# CIRULO_PANEL.net
KiCad netlist of a schematic drawn in EAGLE
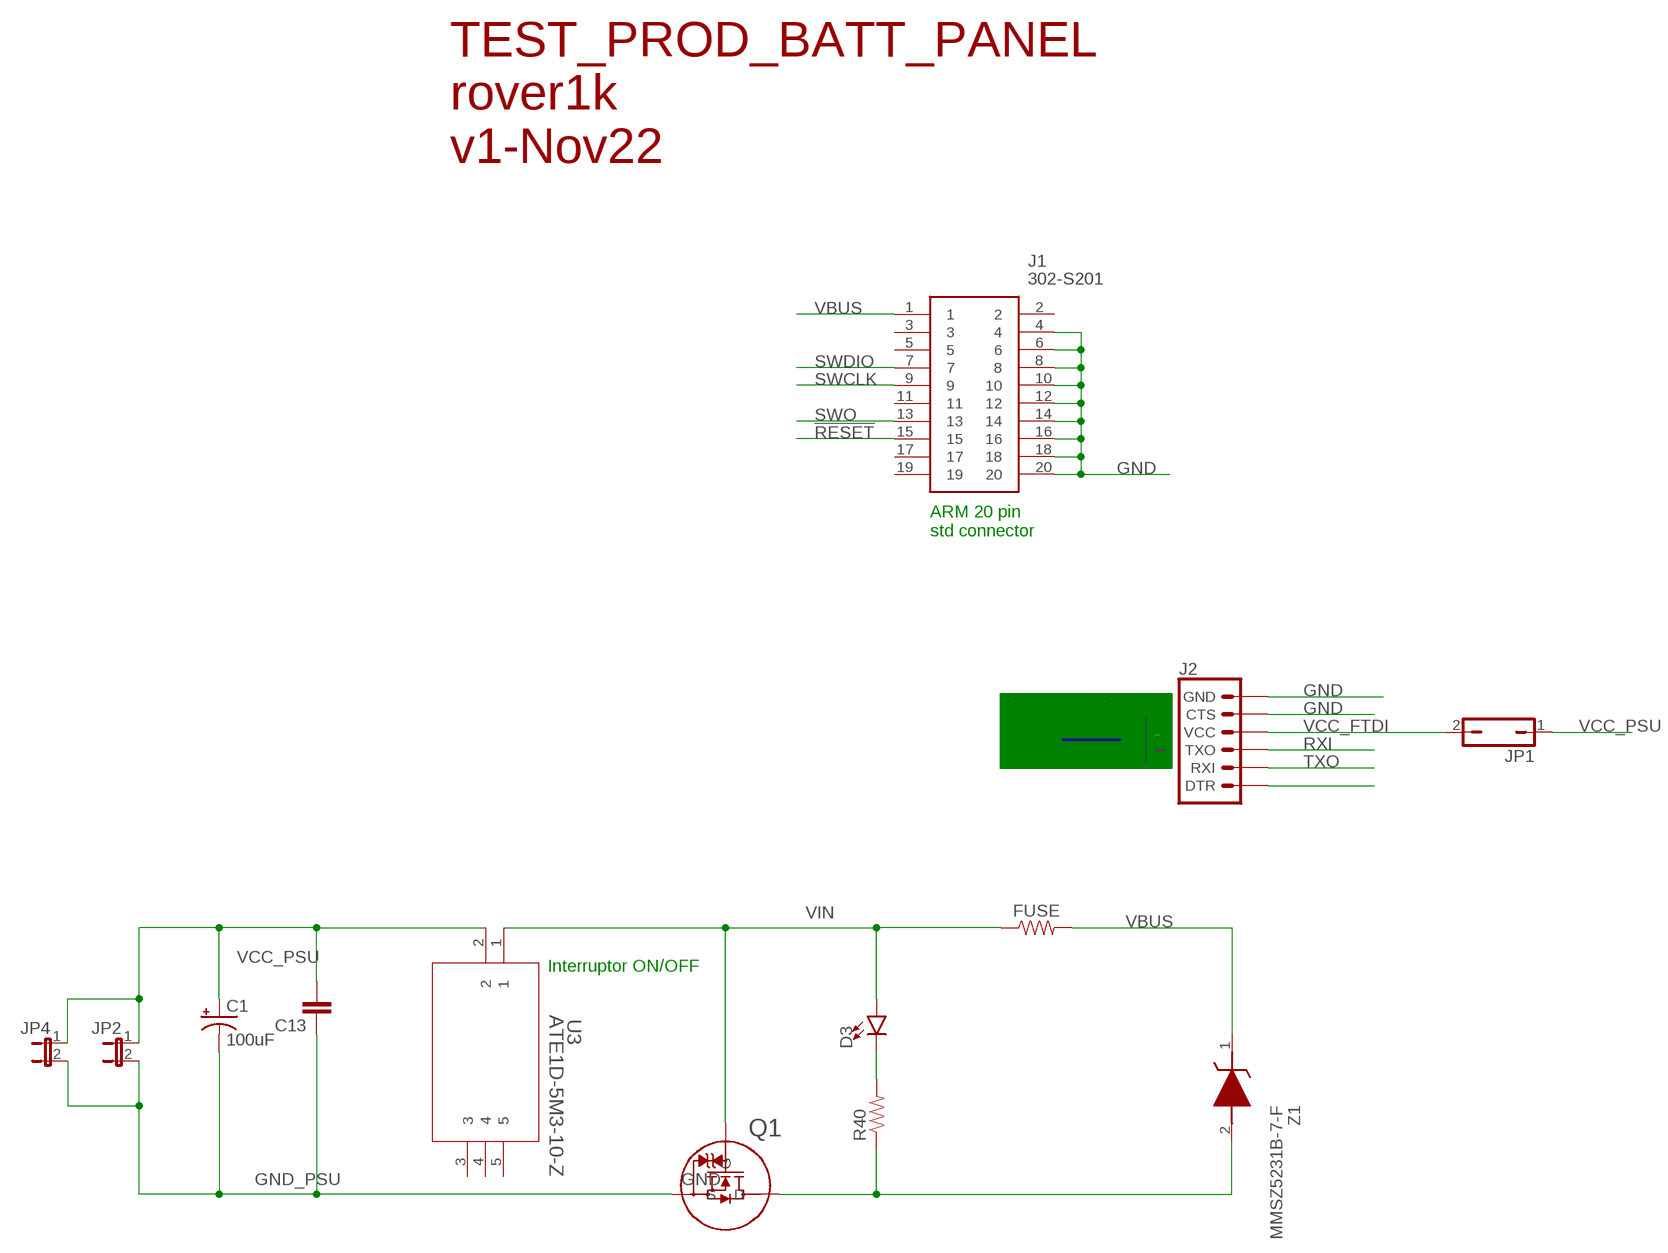
[diagram p0: schematic, sheet 1]

(export (version "E")
  (design (tool "Eeschema 10.0.6"))
  (components
    (comp (ref "C1")
      (value "100uF")
      (footprint "eagle-import:CPOL-RADIAL-2.5MM-6.5MM")
      (libsource (lib "eagle-import") (part "100UF-POLAR-RADIAL-2.5MM-25V-20%"))
    )
    (comp (ref "C13")
      (value "C-EUC0805")
      (footprint "eagle-import:C0805")
      (libsource (lib "eagle-import") (part "C-EUC0805"))
    )
    (comp (ref "D3")
      (value "LED3MM")
      (footprint "eagle-import:LED_3MM")
      (libsource (lib "eagle-import") (part "LED3MM"))
    )
    (comp (ref "FUSE")
      (value "RESISTOR0805")
      (footprint "eagle-import:0805")
      (libsource (lib "eagle-import") (part "RESISTOR0805"))
    )
    (comp (ref "J1")
      (value "302-S201")
      (footprint "eagle-import:SHDR20W66P254_2X10_3300X905X90")
      (libsource (lib "eagle-import") (part "302-S201"))
    )
    (comp (ref "J2")
      (value "6_PIN_SERIAL_TARGET")
      (footprint "eagle-import:1X06")
      (libsource (lib "eagle-import") (part "6_PIN_SERIAL_TARGET"))
    )
    (comp (ref "JP1")
      (value "JP1Q")
      (footprint "eagle-import:JP1")
      (libsource (lib "eagle-import") (part "JP1Q"))
    )
    (comp (ref "JP2")
      (value "JP1E")
      (footprint "eagle-import:JP1")
      (libsource (lib "eagle-import") (part "JP1E"))
    )
    (comp (ref "JP4")
      (value "JP1E")
      (footprint "eagle-import:JP1")
      (libsource (lib "eagle-import") (part "JP1E"))
    )
    (comp (ref "Q1")
      (value "PJA3416AE_R1_00001")
      (footprint "eagle-import:SOT23_PJA3416_PNJ")
      (fields (field (name "COPYRIGHT") "Copyright (C) 2022 Ultra Librarian. All rights reserved."))
      (libsource (lib "eagle-import") (part "PJA3416AE_R1_00001"))
    )
    (comp (ref "R40")
      (value "10K")
      (footprint "eagle-import:0805")
      (libsource (lib "eagle-import") (part "RESISTOR0805-RES"))
    )
    (comp (ref "U3")
      (value "ATE1D-5M3-10-Z")
      (footprint "eagle-import:SPDT05_ATE1D_9P5X8_NDC")
      (fields (field (name "COPYRIGHT") "Copyright (C) 2022 Ultra Librarian. All rights reserved."))
      (libsource (lib "eagle-import") (part "ATE1D-5M3-10-Z"))
    )
    (comp (ref "Z1")
      (value "MMSZ5231B-7-F")
      (footprint "eagle-import:SOD3716X145N")
      (fields (field (name "MOUSER_PART_NUMBER") "621-MMSZ5231B-F"))
      (libsource (lib "eagle-import") (part "MMSZ5231B-7-F"))
    )
  )
  (nets
    (net (code "1") (name "/GND") (class "Default")
      (node (ref "J1") (pin "10") (pinfunction "10_10") (pintype "bidirectional"))
      (node (ref "J1") (pin "12") (pinfunction "12_12") (pintype "bidirectional"))
      (node (ref "J1") (pin "14") (pinfunction "14_14") (pintype "bidirectional"))
      (node (ref "J1") (pin "16") (pinfunction "16_16") (pintype "bidirectional"))
      (node (ref "J1") (pin "18") (pinfunction "18_18") (pintype "bidirectional"))
      (node (ref "J1") (pin "20") (pinfunction "20_20") (pintype "bidirectional"))
      (node (ref "J1") (pin "4") (pinfunction "4_4") (pintype "bidirectional"))
      (node (ref "J1") (pin "6") (pinfunction "6_6") (pintype "bidirectional"))
      (node (ref "J1") (pin "8") (pinfunction "8_8") (pintype "bidirectional"))
      (node (ref "J2") (pin "5") (pinfunction "CTS_5") (pintype "passive"))
      (node (ref "J2") (pin "6") (pinfunction "GND_6") (pintype "passive"))
      (node (ref "Q1") (pin "3") (pinfunction "D_3") (pintype "passive"))
      (node (ref "R40") (pin "1") (pinfunction "1_1") (pintype "passive"))
      (node (ref "Z1") (pin "2") (pinfunction "A_2") (pintype "bidirectional"))
    )
    (net (code "2") (name "/GND_PSU") (class "Default")
      (node (ref "C1") (pin "2") (pinfunction "-_2") (pintype "passive"))
      (node (ref "C13") (pin "1") (pinfunction "1_1") (pintype "passive"))
      (node (ref "JP2") (pin "2") (pinfunction "2_2") (pintype "passive"))
      (node (ref "JP4") (pin "2") (pinfunction "2_2") (pintype "passive"))
      (node (ref "Q1") (pin "2") (pinfunction "S_2") (pintype "passive"))
    )
    (net (code "3") (name "/RXI") (class "Default")
      (node (ref "J2") (pin "3") (pinfunction "TXO_3") (pintype "passive"))
    )
    (net (code "4") (name "/SWCLK") (class "Default")
      (node (ref "J1") (pin "9") (pinfunction "9_9") (pintype "bidirectional"))
    )
    (net (code "5") (name "/SWDIO") (class "Default")
      (node (ref "J1") (pin "7") (pinfunction "7_7") (pintype "bidirectional"))
    )
    (net (code "6") (name "/SWO") (class "Default")
      (node (ref "J1") (pin "13") (pinfunction "13_13") (pintype "bidirectional"))
    )
    (net (code "7") (name "/TXO") (class "Default")
      (node (ref "J2") (pin "2") (pinfunction "RXI_2") (pintype "passive"))
    )
    (net (code "8") (name "/VBUS") (class "Default")
      (node (ref "FUSE") (pin "2") (pinfunction "2_2") (pintype "passive"))
      (node (ref "J1") (pin "1") (pinfunction "1_1") (pintype "bidirectional"))
      (node (ref "Z1") (pin "1") (pinfunction "K_1") (pintype "bidirectional"))
    )
    (net (code "9") (name "/VCC_FTDI") (class "Default")
      (node (ref "J2") (pin "4") (pinfunction "VCC_4") (pintype "passive"))
      (node (ref "JP1") (pin "2") (pinfunction "2_2") (pintype "passive"))
    )
    (net (code "10") (name "/VCC_PSU") (class "Default")
      (node (ref "C1") (pin "1") (pinfunction "+_1") (pintype "passive"))
      (node (ref "C13") (pin "2") (pinfunction "2_2") (pintype "passive"))
      (node (ref "JP1") (pin "1") (pinfunction "1_1") (pintype "passive"))
      (node (ref "JP2") (pin "1") (pinfunction "1_1") (pintype "passive"))
      (node (ref "JP4") (pin "1") (pinfunction "1_1") (pintype "passive"))
      (node (ref "U3") (pin "2") (pinfunction "2_2") (pintype "passive"))
    )
    (net (code "11") (name "/VIN") (class "Default")
      (node (ref "D3") (pin "A") (pinfunction "A_A") (pintype "passive"))
      (node (ref "FUSE") (pin "1") (pinfunction "1_1") (pintype "passive"))
      (node (ref "Q1") (pin "1") (pinfunction "G_1") (pintype "passive"))
      (node (ref "U3") (pin "1") (pinfunction "1_1") (pintype "passive"))
    )
    (net (code "12") (name "/~{RESET}") (class "Default")
      (node (ref "J1") (pin "15") (pinfunction "15_15") (pintype "bidirectional"))
    )
    (net (code "13") (name "Net-(D3-C)") (class "Default")
      (node (ref "D3") (pin "K") (pinfunction "C_K") (pintype "passive"))
      (node (ref "R40") (pin "2") (pinfunction "2_2") (pintype "passive"))
    )
    (net (code "14") (name "unconnected-(J1-Pad2)") (class "Default")
      (node (ref "J1") (pin "2") (pinfunction "2_2") (pintype "bidirectional"))
    )
    (net (code "15") (name "unconnected-(J1-Pad3)") (class "Default")
      (node (ref "J1") (pin "3") (pinfunction "3_3") (pintype "bidirectional"))
    )
    (net (code "16") (name "unconnected-(J1-Pad5)") (class "Default")
      (node (ref "J1") (pin "5") (pinfunction "5_5") (pintype "bidirectional"))
    )
    (net (code "17") (name "unconnected-(J1-Pad11)") (class "Default")
      (node (ref "J1") (pin "11") (pinfunction "11_11") (pintype "bidirectional"))
    )
    (net (code "18") (name "unconnected-(J1-Pad17)") (class "Default")
      (node (ref "J1") (pin "17") (pinfunction "17_17") (pintype "bidirectional"))
    )
    (net (code "19") (name "unconnected-(J1-Pad19)") (class "Default")
      (node (ref "J1") (pin "19") (pinfunction "19_19") (pintype "bidirectional"))
    )
    (net (code "20") (name "unconnected-(J2-DTR-Pad1)") (class "Default")
      (node (ref "J2") (pin "1") (pinfunction "DTR_1") (pintype "passive"))
    )
    (net (code "21") (name "unconnected-(U3-Pad3)") (class "Default")
      (node (ref "U3") (pin "3") (pinfunction "3_3") (pintype "passive"))
    )
    (net (code "22") (name "unconnected-(U3-Pad4)") (class "Default")
      (node (ref "U3") (pin "4") (pinfunction "4_4") (pintype "passive"))
    )
    (net (code "23") (name "unconnected-(U3-Pad5)") (class "Default")
      (node (ref "U3") (pin "5") (pinfunction "5_5") (pintype "passive"))
    )
  )
)
